# micrometer_parallelism.net
KiCad netlist of a schematic drawn in EasyEDA
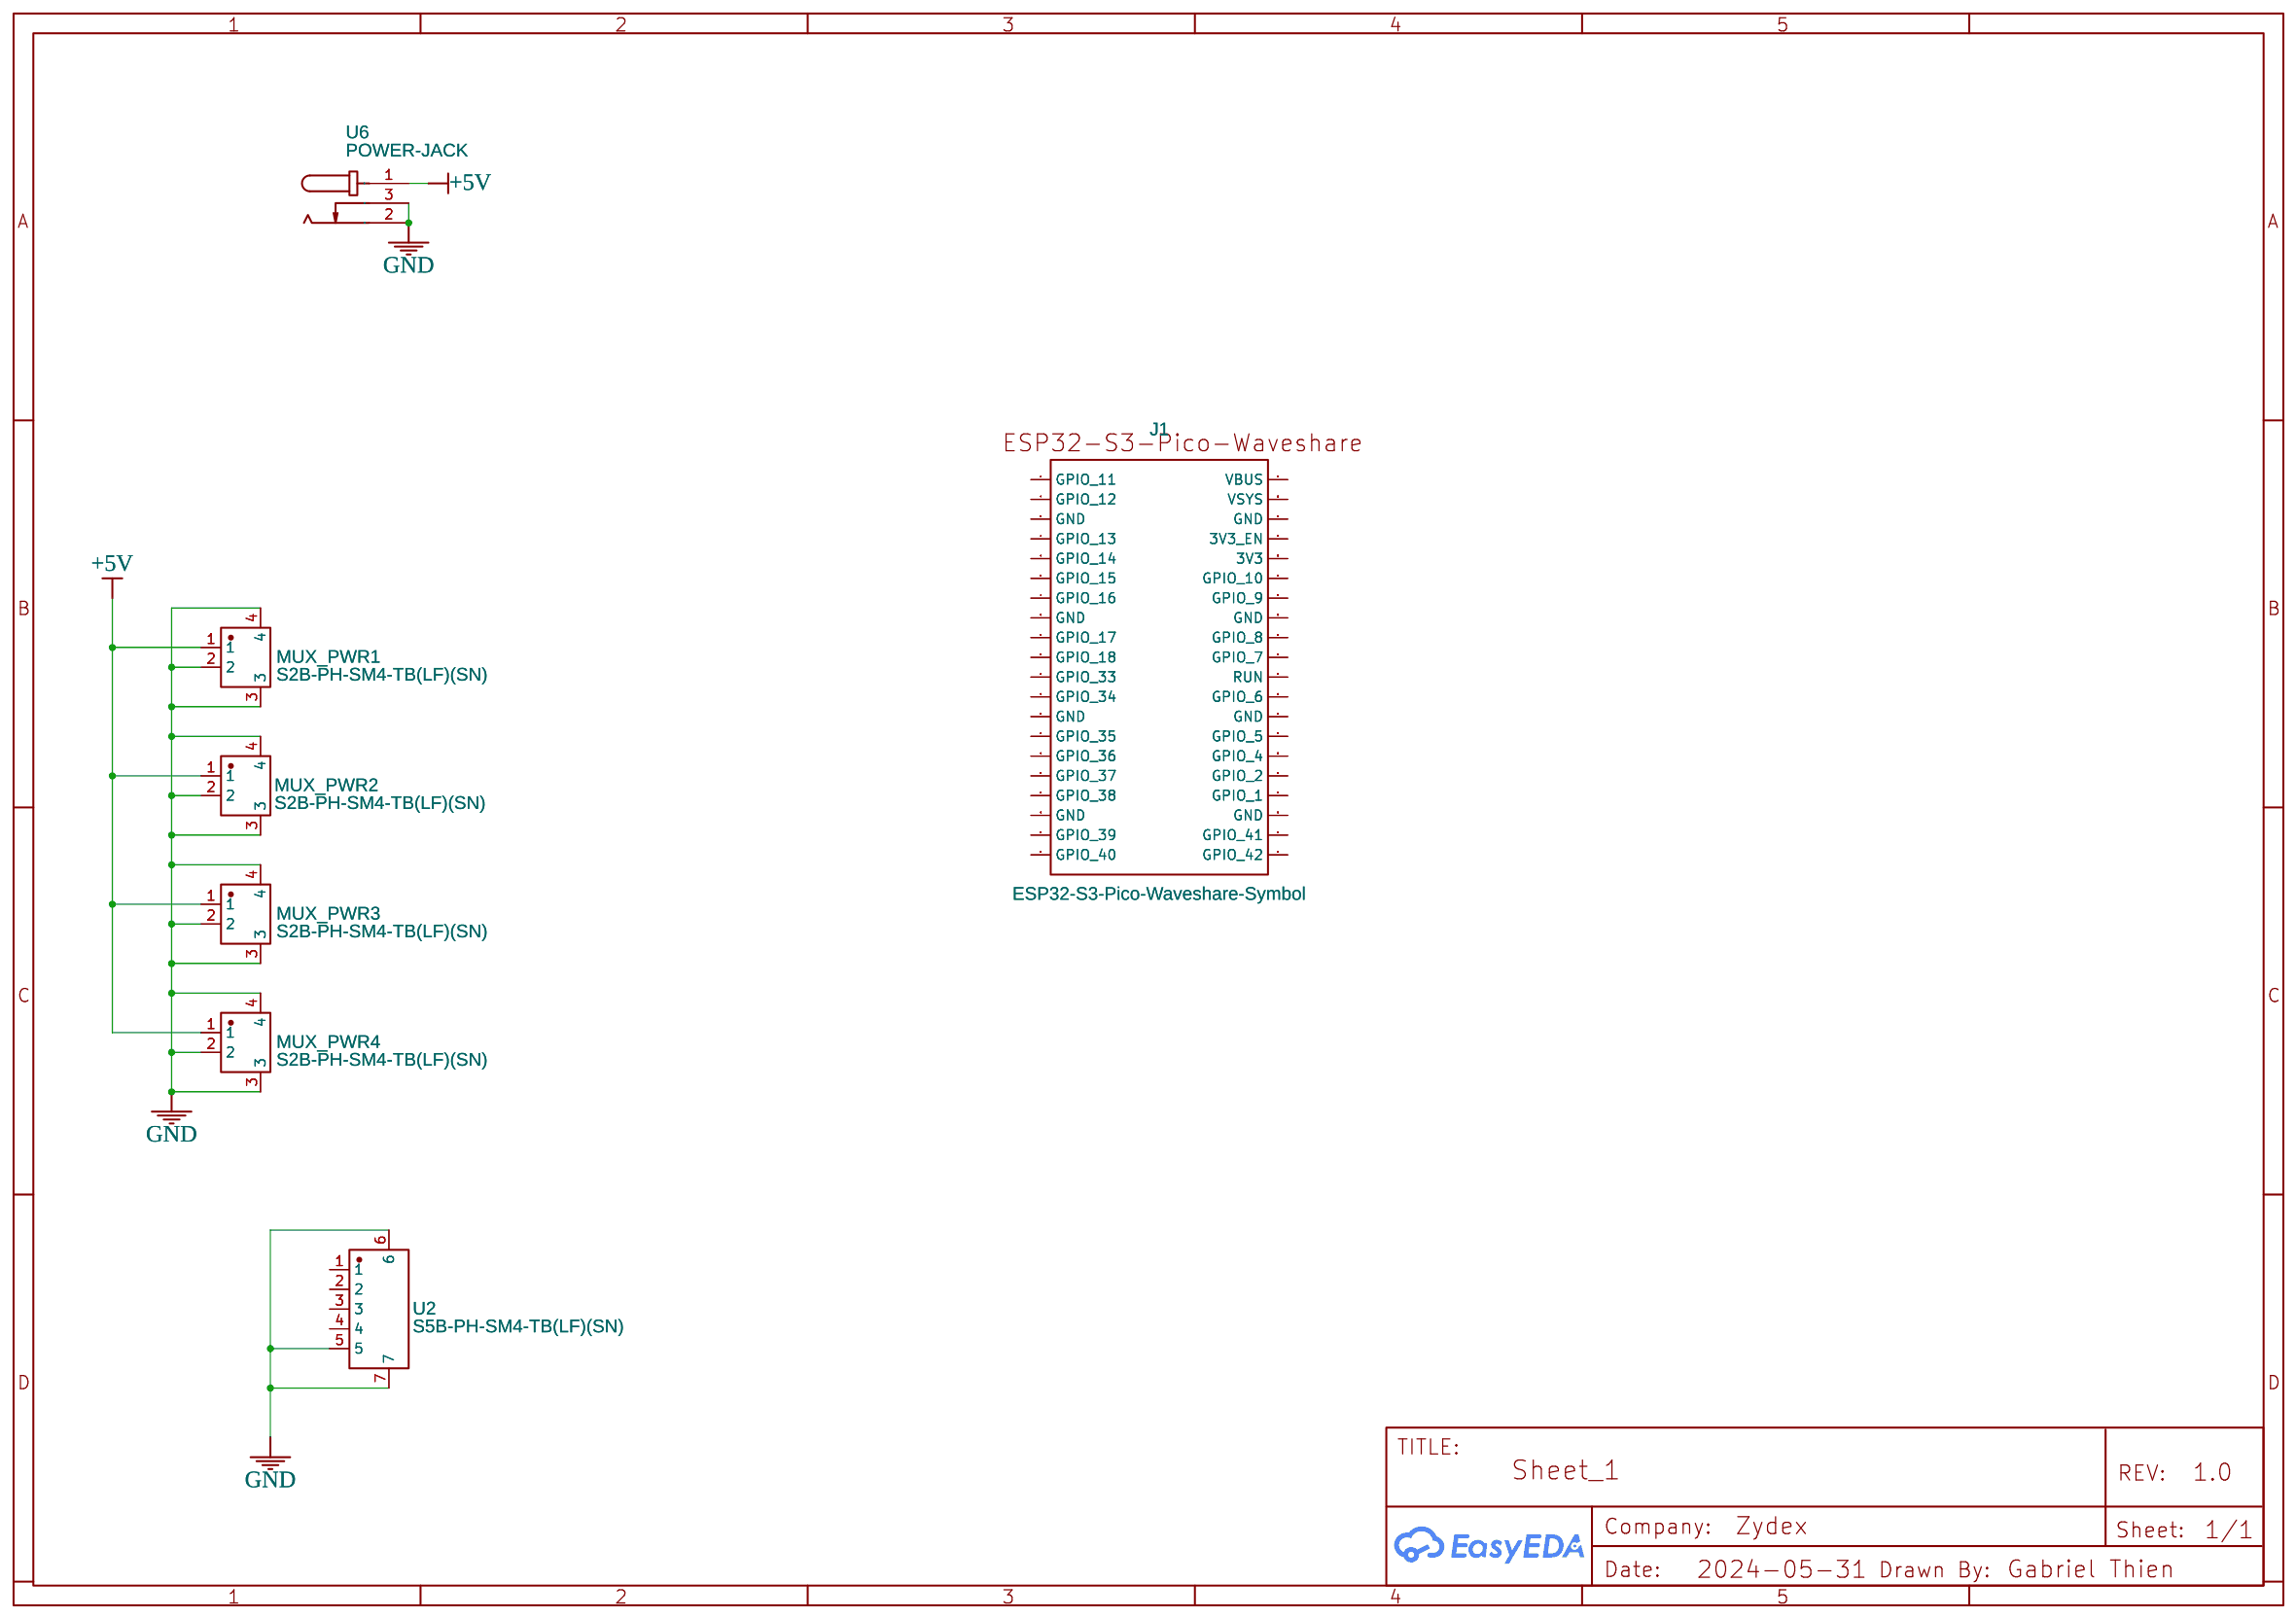
[diagram p0: schematic sheet]

(export (version "E")
  (design (tool "Eeschema 10.0.6"))
  (components
    (comp (ref "J1")
      (value "ESP32-S3-Pico-Waveshare-Symbol")
      (fields (field (name "Manufacturer") "Waveshare"))
      (libsource (lib "") (part "ESP32-S3-Pico-Waveshare-Symbol"))
    )
    (comp (ref "MUX_PWR1")
      (value "S2B-PH-SM4-TB(LF)(SN)")
      (fields (field (name "Manufacturer") "JST"))
      (libsource (lib "") (part "S2B-PH-SM4-TB(LF)(SN)"))
    )
    (comp (ref "MUX_PWR2")
      (value "S2B-PH-SM4-TB(LF)(SN)")
      (fields (field (name "Manufacturer") "JST"))
      (libsource (lib "") (part "S2B-PH-SM4-TB(LF)(SN)"))
    )
    (comp (ref "MUX_PWR3")
      (value "S2B-PH-SM4-TB(LF)(SN)")
      (fields (field (name "Manufacturer") "JST"))
      (libsource (lib "") (part "S2B-PH-SM4-TB(LF)(SN)"))
    )
    (comp (ref "MUX_PWR4")
      (value "S2B-PH-SM4-TB(LF)(SN)")
      (fields (field (name "Manufacturer") "JST"))
      (libsource (lib "") (part "S2B-PH-SM4-TB(LF)(SN)"))
    )
    (comp (ref "U2")
      (value "S5B-PH-SM4-TB(LF)(SN)")
      (fields (field (name "Manufacturer") "JST"))
      (libsource (lib "") (part "S5B-PH-SM4-TB(LF)(SN)"))
    )
    (comp (ref "U6")
      (value "POWER-JACK")
      (fields (field (name "Manufacturer") "索峰"))
      (libsource (lib "") (part "POWER-JACK"))
    )
  )
  (nets
    (net (code "1") (name "+5V") (class "Default")
      (node (ref "MUX_PWR1") (pin "1") (pinfunction "1_1") (pintype "unspecified"))
      (node (ref "MUX_PWR2") (pin "1") (pinfunction "1_1") (pintype "unspecified"))
      (node (ref "MUX_PWR3") (pin "1") (pinfunction "1_1") (pintype "unspecified"))
      (node (ref "MUX_PWR4") (pin "1") (pinfunction "1_1") (pintype "unspecified"))
      (node (ref "U6") (pin "1") (pinfunction "1_1") (pintype "unspecified"))
    )
    (net (code "2") (name "GND") (class "Default")
      (node (ref "MUX_PWR1") (pin "2") (pinfunction "2_2") (pintype "unspecified"))
      (node (ref "MUX_PWR1") (pin "3") (pinfunction "3_3") (pintype "unspecified"))
      (node (ref "MUX_PWR1") (pin "4") (pinfunction "4_4") (pintype "unspecified"))
      (node (ref "MUX_PWR2") (pin "2") (pinfunction "2_2") (pintype "unspecified"))
      (node (ref "MUX_PWR2") (pin "3") (pinfunction "3_3") (pintype "unspecified"))
      (node (ref "MUX_PWR2") (pin "4") (pinfunction "4_4") (pintype "unspecified"))
      (node (ref "MUX_PWR3") (pin "2") (pinfunction "2_2") (pintype "unspecified"))
      (node (ref "MUX_PWR3") (pin "3") (pinfunction "3_3") (pintype "unspecified"))
      (node (ref "MUX_PWR3") (pin "4") (pinfunction "4_4") (pintype "unspecified"))
      (node (ref "MUX_PWR4") (pin "2") (pinfunction "2_2") (pintype "unspecified"))
      (node (ref "MUX_PWR4") (pin "3") (pinfunction "3_3") (pintype "unspecified"))
      (node (ref "MUX_PWR4") (pin "4") (pinfunction "4_4") (pintype "unspecified"))
      (node (ref "U2") (pin "5") (pinfunction "5_5") (pintype "unspecified"))
      (node (ref "U2") (pin "6") (pinfunction "6_6") (pintype "unspecified"))
      (node (ref "U2") (pin "7") (pinfunction "7_7") (pintype "unspecified"))
      (node (ref "U6") (pin "2") (pinfunction "2_2") (pintype "unspecified"))
      (node (ref "U6") (pin "3") (pinfunction "3_3") (pintype "unspecified"))
    )
    (net (code "3") (name "unconnected-(J1-3V3-Pad36)") (class "Default")
      (node (ref "J1") (pin "36") (pinfunction "3V3_36") (pintype "unspecified"))
    )
    (net (code "4") (name "unconnected-(J1-3V3_EN-Pad37)") (class "Default")
      (node (ref "J1") (pin "37") (pinfunction "3V3_EN_37") (pintype "unspecified"))
    )
    (net (code "5") (name "unconnected-(J1-GND-Pad3)") (class "Default")
      (node (ref "J1") (pin "3") (pinfunction "GND_3") (pintype "unspecified"))
    )
    (net (code "6") (name "unconnected-(J1-GND-Pad8)") (class "Default")
      (node (ref "J1") (pin "8") (pinfunction "GND_8") (pintype "unspecified"))
    )
    (net (code "7") (name "unconnected-(J1-GND-Pad13)") (class "Default")
      (node (ref "J1") (pin "13") (pinfunction "GND_13") (pintype "unspecified"))
    )
    (net (code "8") (name "unconnected-(J1-GND-Pad18)") (class "Default")
      (node (ref "J1") (pin "18") (pinfunction "GND_18") (pintype "unspecified"))
    )
    (net (code "9") (name "unconnected-(J1-GND-Pad23)") (class "Default")
      (node (ref "J1") (pin "23") (pinfunction "GND_23") (pintype "unspecified"))
    )
    (net (code "10") (name "unconnected-(J1-GND-Pad28)") (class "Default")
      (node (ref "J1") (pin "28") (pinfunction "GND_28") (pintype "unspecified"))
    )
    (net (code "11") (name "unconnected-(J1-GND-Pad33)") (class "Default")
      (node (ref "J1") (pin "33") (pinfunction "GND_33") (pintype "unspecified"))
    )
    (net (code "12") (name "unconnected-(J1-GND-Pad38)") (class "Default")
      (node (ref "J1") (pin "38") (pinfunction "GND_38") (pintype "unspecified"))
    )
    (net (code "13") (name "unconnected-(J1-GPIO_1-Pad24)") (class "Default")
      (node (ref "J1") (pin "24") (pinfunction "GPIO_1_24") (pintype "unspecified"))
    )
    (net (code "14") (name "unconnected-(J1-GPIO_2-Pad25)") (class "Default")
      (node (ref "J1") (pin "25") (pinfunction "GPIO_2_25") (pintype "unspecified"))
    )
    (net (code "15") (name "unconnected-(J1-GPIO_4-Pad26)") (class "Default")
      (node (ref "J1") (pin "26") (pinfunction "GPIO_4_26") (pintype "unspecified"))
    )
    (net (code "16") (name "unconnected-(J1-GPIO_5-Pad27)") (class "Default")
      (node (ref "J1") (pin "27") (pinfunction "GPIO_5_27") (pintype "unspecified"))
    )
    (net (code "17") (name "unconnected-(J1-GPIO_6-Pad29)") (class "Default")
      (node (ref "J1") (pin "29") (pinfunction "GPIO_6_29") (pintype "unspecified"))
    )
    (net (code "18") (name "unconnected-(J1-GPIO_7-Pad31)") (class "Default")
      (node (ref "J1") (pin "31") (pinfunction "GPIO_7_31") (pintype "unspecified"))
    )
    (net (code "19") (name "unconnected-(J1-GPIO_8-Pad32)") (class "Default")
      (node (ref "J1") (pin "32") (pinfunction "GPIO_8_32") (pintype "unspecified"))
    )
    (net (code "20") (name "unconnected-(J1-GPIO_9-Pad34)") (class "Default")
      (node (ref "J1") (pin "34") (pinfunction "GPIO_9_34") (pintype "unspecified"))
    )
    (net (code "21") (name "unconnected-(J1-GPIO_10-Pad35)") (class "Default")
      (node (ref "J1") (pin "35") (pinfunction "GPIO_10_35") (pintype "unspecified"))
    )
    (net (code "22") (name "unconnected-(J1-GPIO_11-Pad1)") (class "Default")
      (node (ref "J1") (pin "1") (pinfunction "GPIO_11_1") (pintype "unspecified"))
    )
    (net (code "23") (name "unconnected-(J1-GPIO_12-Pad2)") (class "Default")
      (node (ref "J1") (pin "2") (pinfunction "GPIO_12_2") (pintype "unspecified"))
    )
    (net (code "24") (name "unconnected-(J1-GPIO_13-Pad4)") (class "Default")
      (node (ref "J1") (pin "4") (pinfunction "GPIO_13_4") (pintype "unspecified"))
    )
    (net (code "25") (name "unconnected-(J1-GPIO_14-Pad5)") (class "Default")
      (node (ref "J1") (pin "5") (pinfunction "GPIO_14_5") (pintype "unspecified"))
    )
    (net (code "26") (name "unconnected-(J1-GPIO_15-Pad6)") (class "Default")
      (node (ref "J1") (pin "6") (pinfunction "GPIO_15_6") (pintype "unspecified"))
    )
    (net (code "27") (name "unconnected-(J1-GPIO_16-Pad7)") (class "Default")
      (node (ref "J1") (pin "7") (pinfunction "GPIO_16_7") (pintype "unspecified"))
    )
    (net (code "28") (name "unconnected-(J1-GPIO_17-Pad9)") (class "Default")
      (node (ref "J1") (pin "9") (pinfunction "GPIO_17_9") (pintype "unspecified"))
    )
    (net (code "29") (name "unconnected-(J1-GPIO_18-Pad10)") (class "Default")
      (node (ref "J1") (pin "10") (pinfunction "GPIO_18_10") (pintype "unspecified"))
    )
    (net (code "30") (name "unconnected-(J1-GPIO_33-Pad11)") (class "Default")
      (node (ref "J1") (pin "11") (pinfunction "GPIO_33_11") (pintype "unspecified"))
    )
    (net (code "31") (name "unconnected-(J1-GPIO_34-Pad12)") (class "Default")
      (node (ref "J1") (pin "12") (pinfunction "GPIO_34_12") (pintype "unspecified"))
    )
    (net (code "32") (name "unconnected-(J1-GPIO_35-Pad14)") (class "Default")
      (node (ref "J1") (pin "14") (pinfunction "GPIO_35_14") (pintype "unspecified"))
    )
    (net (code "33") (name "unconnected-(J1-GPIO_36-Pad15)") (class "Default")
      (node (ref "J1") (pin "15") (pinfunction "GPIO_36_15") (pintype "unspecified"))
    )
    (net (code "34") (name "unconnected-(J1-GPIO_37-Pad16)") (class "Default")
      (node (ref "J1") (pin "16") (pinfunction "GPIO_37_16") (pintype "unspecified"))
    )
    (net (code "35") (name "unconnected-(J1-GPIO_38-Pad17)") (class "Default")
      (node (ref "J1") (pin "17") (pinfunction "GPIO_38_17") (pintype "unspecified"))
    )
    (net (code "36") (name "unconnected-(J1-GPIO_39-Pad19)") (class "Default")
      (node (ref "J1") (pin "19") (pinfunction "GPIO_39_19") (pintype "unspecified"))
    )
    (net (code "37") (name "unconnected-(J1-GPIO_40-Pad20)") (class "Default")
      (node (ref "J1") (pin "20") (pinfunction "GPIO_40_20") (pintype "unspecified"))
    )
    (net (code "38") (name "unconnected-(J1-GPIO_41-Pad22)") (class "Default")
      (node (ref "J1") (pin "22") (pinfunction "GPIO_41_22") (pintype "unspecified"))
    )
    (net (code "39") (name "unconnected-(J1-GPIO_42-Pad21)") (class "Default")
      (node (ref "J1") (pin "21") (pinfunction "GPIO_42_21") (pintype "unspecified"))
    )
    (net (code "40") (name "unconnected-(J1-RUN-Pad30)") (class "Default")
      (node (ref "J1") (pin "30") (pinfunction "RUN_30") (pintype "unspecified"))
    )
    (net (code "41") (name "unconnected-(J1-VBUS-Pad40)") (class "Default")
      (node (ref "J1") (pin "40") (pinfunction "VBUS_40") (pintype "unspecified"))
    )
    (net (code "42") (name "unconnected-(J1-VSYS-Pad39)") (class "Default")
      (node (ref "J1") (pin "39") (pinfunction "VSYS_39") (pintype "unspecified"))
    )
    (net (code "43") (name "unconnected-(U2-Pad1)") (class "Default")
      (node (ref "U2") (pin "1") (pinfunction "1_1") (pintype "unspecified"))
    )
    (net (code "44") (name "unconnected-(U2-Pad2)") (class "Default")
      (node (ref "U2") (pin "2") (pinfunction "2_2") (pintype "unspecified"))
    )
    (net (code "45") (name "unconnected-(U2-Pad3)") (class "Default")
      (node (ref "U2") (pin "3") (pinfunction "3_3") (pintype "unspecified"))
    )
    (net (code "46") (name "unconnected-(U2-Pad4)") (class "Default")
      (node (ref "U2") (pin "4") (pinfunction "4_4") (pintype "unspecified"))
    )
  )
)
